# Si5504DC_breakout.net
KiCad netlist of a schematic drawn in EAGLE
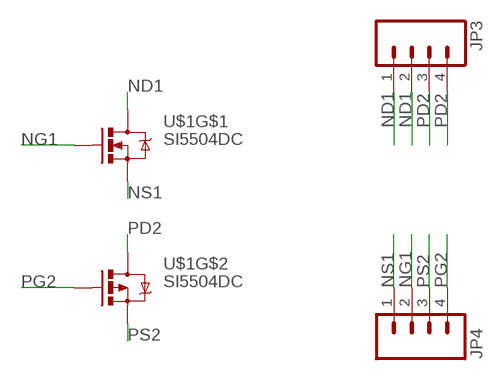
[diagram p0: schematic, sheet 1]

(export (version "E")
  (design (tool "Eeschema 10.0.6"))
  (components
    (comp (ref "JP3")
      (value "M04LOCK")
      (footprint "eagle-import:1X04_LOCK")
      (libsource (lib "eagle-import") (part "M04LOCK"))
    )
    (comp (ref "JP4")
      (value "M04LOCK")
      (footprint "eagle-import:1X04_LOCK")
      (libsource (lib "eagle-import") (part "M04LOCK"))
    )
    (comp (ref "U$1")
      (value "SI5504DC")
      (footprint "eagle-import:1206-8")
      (libsource (lib "eagle-import") (part "SI5504DC"))
    )
  )
  (nets
    (net (code "1") (name "/ND1") (class "Default")
      (node (ref "JP3") (pin "1") (pinfunction "1_1") (pintype "passive"))
      (node (ref "JP3") (pin "2") (pinfunction "2_2") (pintype "passive"))
      (node (ref "U$1") (pin "P$7") (pinfunction "D_P$7") (pintype "passive"))
      (node (ref "U$1") (pin "P$8") (pinfunction "D_P$8") (pintype "passive"))
    )
    (net (code "2") (name "/NG1") (class "Default")
      (node (ref "JP4") (pin "2") (pinfunction "2_2") (pintype "passive"))
      (node (ref "U$1") (pin "P$2") (pinfunction "G_P$2") (pintype "passive"))
    )
    (net (code "3") (name "/NS1") (class "Default")
      (node (ref "JP4") (pin "1") (pinfunction "1_1") (pintype "passive"))
      (node (ref "U$1") (pin "P$1") (pinfunction "S_P$1") (pintype "passive"))
    )
    (net (code "4") (name "/PD2") (class "Default")
      (node (ref "JP3") (pin "3") (pinfunction "3_3") (pintype "passive"))
      (node (ref "JP3") (pin "4") (pinfunction "4_4") (pintype "passive"))
      (node (ref "U$1") (pin "P$5") (pinfunction "D_P$5") (pintype "passive"))
      (node (ref "U$1") (pin "P$6") (pinfunction "D_P$6") (pintype "passive"))
    )
    (net (code "5") (name "/PG2") (class "Default")
      (node (ref "JP4") (pin "4") (pinfunction "4_4") (pintype "passive"))
      (node (ref "U$1") (pin "P$4") (pinfunction "G_P$4") (pintype "passive"))
    )
    (net (code "6") (name "/PS2") (class "Default")
      (node (ref "JP4") (pin "3") (pinfunction "3_3") (pintype "passive"))
      (node (ref "U$1") (pin "P$3") (pinfunction "S_P$3") (pintype "passive"))
    )
  )
)
